# sha2017_rev1_0_0_0.net
KiCad netlist of a schematic drawn in Altium Designer
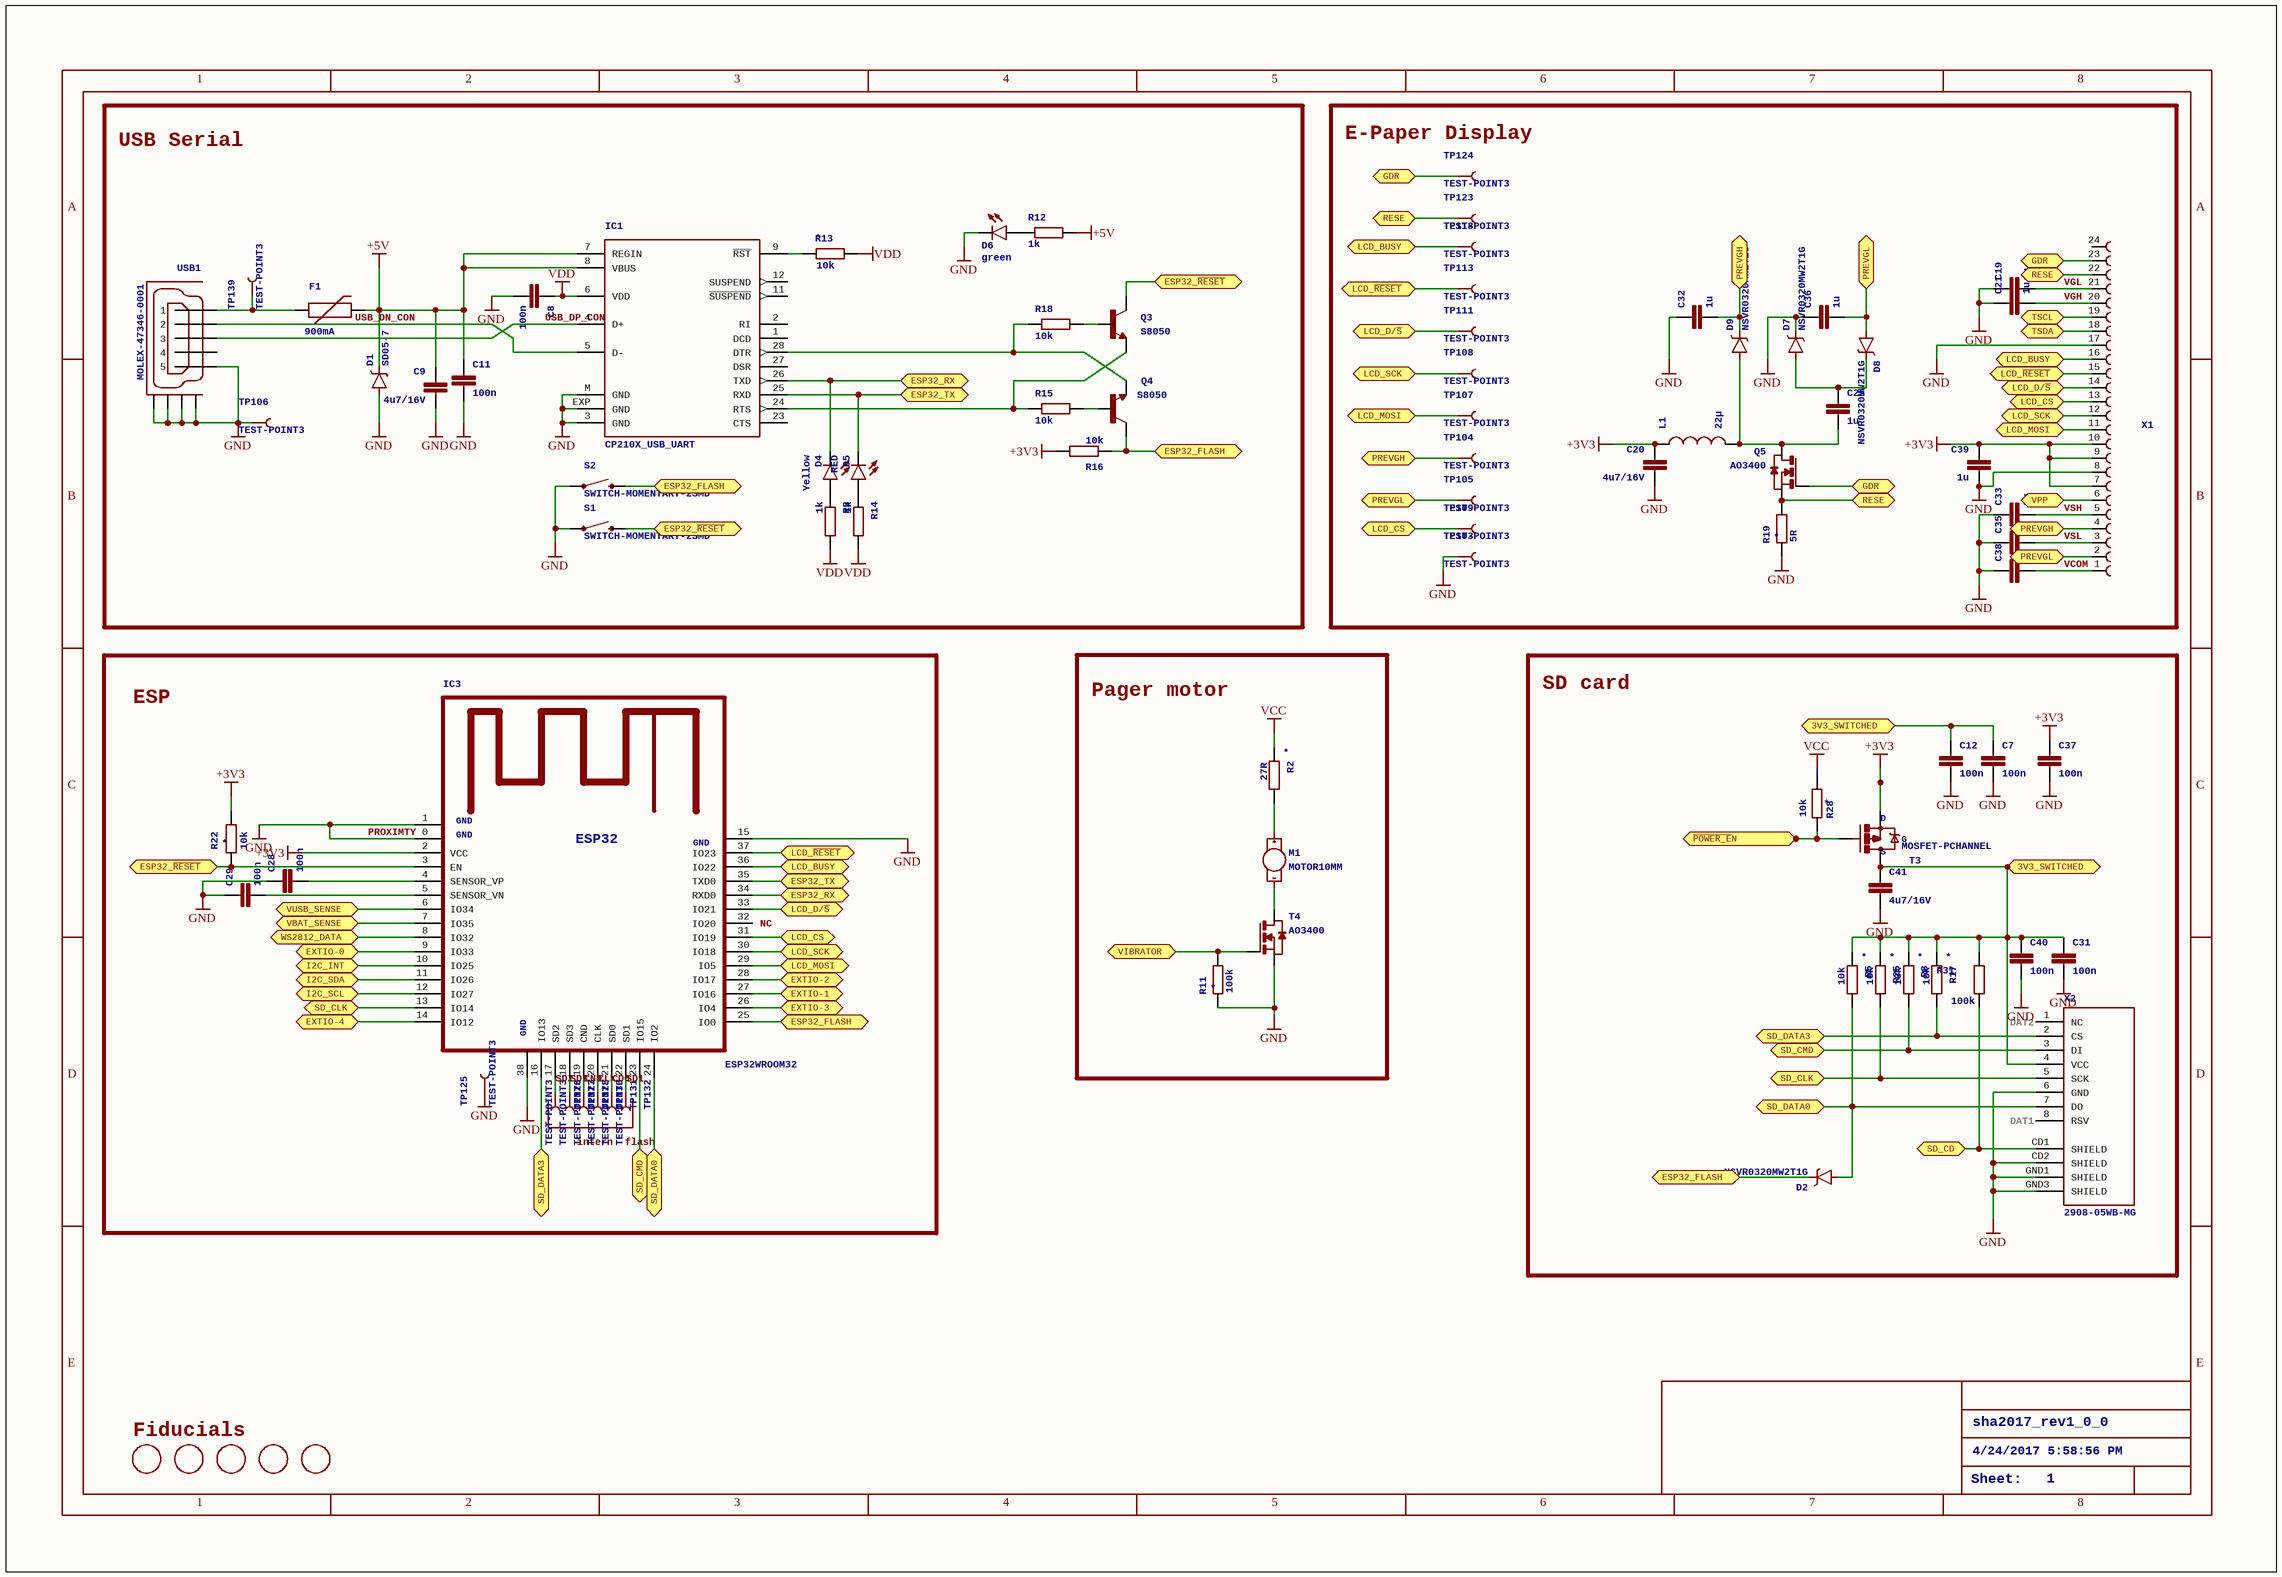
[diagram p0: sha2017_rev1_0_0_0.SchDoc]

(export (version "E")
  (design (tool "Eeschema 10.0.6"))
  (components
    (comp (ref "C7") (value "100n") (footprint "C0603-DASHES") (libsource (lib "") (part "C0603-DASHES_1")))
    (comp (ref "C8") (value "100n") (footprint "C0603-DASHES") (libsource (lib "") (part "C0603-DASHES_2")))
    (comp (ref "C9")
      (value "4u7/16V")
      (footprint "C0805")
      (description "CAPACITOR, European symbol")
      (libsource (lib "rcl") (part "C-EUC0805"))
    )
    (comp (ref "C11") (value "100n") (footprint "C0603-DASHES") (libsource (lib "") (part "C0603-DASHES_1")))
    (comp (ref "C12") (value "100n") (footprint "C0603-DASHES") (libsource (lib "") (part "C0603-DASHES_1")))
    (comp (ref "C19")
      (value "1u")
      (footprint "C0603-DASHES")
      (libsource (lib "sha2017_rev0_1_0_dev") (part "C0603-DASHES"))
    )
    (comp (ref "C20")
      (value "4u7/16V")
      (footprint "C0805")
      (description "CAPACITOR, European symbol")
      (libsource (lib "rcl") (part "C-EUC0805"))
    )
    (comp (ref "C21")
      (value "1u")
      (footprint "C0603-DASHES")
      (libsource (lib "sha2017_rev0_1_0_dev") (part "C0603-DASHES"))
    )
    (comp (ref "C25") (value "1u") (footprint "C0603-DASHES") (libsource (lib "") (part "C0603-DASHES_1")))
    (comp (ref "C28")
      (value "100n")
      (footprint "C0603-DASHES")
      (libsource (lib "sha2017_rev0_1_0_dev") (part "C0603-DASHES"))
    )
    (comp (ref "C29")
      (value "100n")
      (footprint "C0603-DASHES")
      (libsource (lib "sha2017_rev0_1_0_dev") (part "C0603-DASHES"))
    )
    (comp (ref "C31") (value "100n") (footprint "C0603-DASHES") (libsource (lib "") (part "C0603-DASHES_1")))
    (comp (ref "C32")
      (value "1u")
      (footprint "C0603-DASHES")
      (libsource (lib "sha2017_rev0_1_0_dev") (part "C0603-DASHES"))
    )
    (comp (ref "C33")
      (value "1u")
      (footprint "C0603-DASHES")
      (libsource (lib "sha2017_rev0_1_0_dev") (part "C0603-DASHES"))
    )
    (comp (ref "C35")
      (value "1u")
      (footprint "C0603-DASHES")
      (libsource (lib "sha2017_rev0_1_0_dev") (part "C0603-DASHES"))
    )
    (comp (ref "C36")
      (value "1u")
      (footprint "C0603-DASHES")
      (libsource (lib "sha2017_rev0_1_0_dev") (part "C0603-DASHES"))
    )
    (comp (ref "C37") (value "100n") (footprint "C0603-DASHES") (libsource (lib "") (part "C0603-DASHES_1")))
    (comp (ref "C38")
      (value "1u")
      (footprint "C0603-DASHES")
      (libsource (lib "sha2017_rev0_1_0_dev") (part "C0603-DASHES"))
    )
    (comp (ref "C39") (value "1u") (footprint "C0603-DASHES") (libsource (lib "") (part "C0603-DASHES_2")))
    (comp (ref "C40") (value "100n") (footprint "C0603-DASHES") (libsource (lib "") (part "C0603-DASHES_1")))
    (comp (ref "C41")
      (value "4u7/16V")
      (footprint "C0805")
      (description "CAPACITOR, European symbol")
      (libsource (lib "") (part "C-EUC0805_1"))
    )
    (comp (ref "D1")
      (value "SD05-7")
      (footprint "SOD-323")
      (libsource (lib "SparkFun-DiscreteSemi") (part "DIODE-SCHOTTKY-PMEG4005EJ"))
    )
    (comp (ref "D2")
      (value "NSVR0320MW2T1G")
      (footprint "SOD-323")
      (description "23V, 1A Schottky diode, SOD-323 package")
      (libsource (lib "SparkFun-DiscreteSemi") (part "BAT20JFILM"))
    )
    (comp (ref "D4")
      (value "Yellow")
      (footprint "LED-0603")
      (libsource (lib "SparkFun-LED") (part "LED0603"))
    )
    (comp (ref "D5") (value "RED") (footprint "LED-0603") (libsource (lib "SparkFun-LED") (part "LED0603")))
    (comp (ref "D6") (value "green") (footprint "LED-0603") (libsource (lib "SparkFun-LED") (part "LED0603")))
    (comp (ref "D7")
      (value "NSVR0320MW2T1G")
      (footprint "SOD-323")
      (description "23V, 1A Schottky diode, SOD-323 package")
      (libsource (lib "SparkFun-DiscreteSemi") (part "BAT20JFILM"))
    )
    (comp (ref "D8")
      (value "NSVR0320MW2T1G")
      (footprint "SOD-323")
      (description "23V, 1A Schottky diode, SOD-323 package")
      (libsource (lib "SparkFun-DiscreteSemi") (part "BAT20JFILM"))
    )
    (comp (ref "D9")
      (value "NSVR0320MW2T1G")
      (footprint "SOD-323")
      (description "23V, 1A Schottky diode, SOD-323 package")
      (libsource (lib "SparkFun-DiscreteSemi") (part "BAT20JFILM"))
    )
    (comp (ref "F1")
      (value "900mA")
      (footprint "PTC-1206")
      (description "Resettable Fuse PTCResettable Fuse. Spark Fun Electronics SKU : COM-08357")
      (libsource (lib "SparkFun-PowerIC") (part "PTCSMD"))
    )
    (comp (ref "FD1")
      (value "FIDUCIAL")
      (footprint "FIDUCIAL_1MM")
      (description "For use by pick and place machines to calibrate the vision/machine, 1mm    By microbuilder.eu")
      (libsource (lib "adafruit") (part "FIDUCIAL"))
    )
    (comp (ref "FD2")
      (value "FIDUCIAL")
      (footprint "FIDUCIAL_1MM")
      (description "For use by pick and place machines to calibrate the vision/machine, 1mm    By microbuilder.eu")
      (libsource (lib "adafruit") (part "FIDUCIAL"))
    )
    (comp (ref "FD3")
      (value "FIDUCIAL")
      (footprint "FIDUCIAL_1MM")
      (description "For use by pick and place machines to calibrate the vision/machine, 1mm    By microbuilder.eu")
      (libsource (lib "adafruit") (part "FIDUCIAL"))
    )
    (comp (ref "FD4")
      (value "FIDUCIAL")
      (footprint "FIDUCIAL_1MM")
      (description "For use by pick and place machines to calibrate the vision/machine, 1mm    By microbuilder.eu")
      (libsource (lib "adafruit") (part "FIDUCIAL"))
    )
    (comp (ref "FD5")
      (value "FIDUCIAL")
      (footprint "FIDUCIAL_1MM")
      (description "For use by pick and place machines to calibrate the vision/machine, 1mm    By microbuilder.eu")
      (libsource (lib "adafruit") (part "FIDUCIAL"))
    )
    (comp (ref "IC1")
      (value "CP210X_USB_UART")
      (footprint "MLP28")
      (libsource (lib "SparkFun-DigitalIC") (part "CP210X_USB_UART"))
    )
    (comp (ref "IC3")
      (value "ESP32WROOM32")
      (footprint "ESP32MOD")
      (fields
        (field (name "ESP32") "ESP32")
        (field (name "GND") "GND")
        (field (name "GND_1") "GND")
        (field (name "GND_2") "GND")
        (field (name "GND_3") "GND")
      )
      (libsource (lib "ESP3x") (part "ESP32WROOM32"))
    )
    (comp (ref "L1")
      (value "22µ")
      (footprint "1210")
      (libsource (lib "SparkFun-Passives") (part "INDUCTOR1210"))
    )
    (comp (ref "M1")
      (value "MOTOR10MM")
      (footprint "VIBE-MOTOR-10MM")
      (libsource (lib "badge") (part "MOTOR10MM"))
    )
    (comp (ref "Q3")
      (value "S8050")
      (footprint "SOT23-3")
      (libsource (lib "SparkFun-DiscreteSemi") (part "TRANSISTOR_NPNMMBT2222A"))
    )
    (comp (ref "Q4")
      (value "S8050")
      (footprint "SOT23-3")
      (libsource (lib "") (part "TRANSISTOR_NPNMMBT2222A_1"))
    )
    (comp (ref "Q5")
      (value "AO3400")
      (footprint "SOT-23")
      (description "MOS FET")
      (libsource (lib "") (part "NMOSSOT23_1"))
    )
    (comp (ref "R2")
      (value "27R")
      (footprint "R0603-DASHES")
      (fields (field (name "NAME") "*"))
      (libsource (lib "00ralf") (part "R0603-DASHES"))
    )
    (comp (ref "R3")
      (value "1k")
      (footprint "R0603-DASHES")
      (libsource (lib "sha2017_rev0_1_0_dev") (part "R0603-DASHES"))
    )
    (comp (ref "R5")
      (value "10k")
      (footprint "R0603-DASHES")
      (fields (field (name "NAME") "*"))
      (libsource (lib "00ralf") (part "R0603-DASHES"))
    )
    (comp (ref "R8")
      (value "10k")
      (footprint "R0603-DASHES")
      (fields (field (name "NAME") "*"))
      (libsource (lib "00ralf") (part "R0603-DASHES"))
    )
    (comp (ref "R11")
      (value "100k")
      (footprint "R0603-DASHES")
      (fields (field (name "NAME") "*"))
      (libsource (lib "00ralf") (part "R0603-DASHES"))
    )
    (comp (ref "R12")
      (value "1k")
      (footprint "R0603-DASHES")
      (libsource (lib "sha2017_rev0_1_0_dev") (part "R0603-DASHES"))
    )
    (comp (ref "R13")
      (value "10k")
      (footprint "R0603-DASHES")
      (fields (field (name "NAME") "*"))
      (libsource (lib "sha2017_rev0_1_0_dev") (part "R0603-DASHES"))
    )
    (comp (ref "R14")
      (value "1k")
      (footprint "R0603-DASHES")
      (libsource (lib "sha2017_rev0_1_0_dev") (part "R0603-DASHES"))
    )
    (comp (ref "R15")
      (value "10k")
      (footprint "R0603-DASHES")
      (libsource (lib "sha2017_rev0_1_0_dev") (part "R0603-DASHES"))
    )
    (comp (ref "R16")
      (value "10k")
      (footprint "R0603-DASHES")
      (libsource (lib "sha2017_rev0_1_0_dev") (part "R0603-DASHES"))
    )
    (comp (ref "R17")
      (value "10k")
      (footprint "R0603-DASHES")
      (fields (field (name "NAME") "*"))
      (libsource (lib "sha2017_rev0_1_0_dev") (part "R0603-DASHES"))
    )
    (comp (ref "R18")
      (value "10k")
      (footprint "R0603-DASHES")
      (libsource (lib "sha2017_rev0_1_0_dev") (part "R0603-DASHES"))
    )
    (comp (ref "R19")
      (value "5R")
      (footprint "R0603-DASHES")
      (fields (field (name "NAME") "*"))
      (libsource (lib "sha2017_rev0_1_0_dev") (part "R0603-DASHES"))
    )
    (comp (ref "R22")
      (value "10k")
      (footprint "R0603-DASHES")
      (fields (field (name "NAME") "*"))
      (libsource (lib "sha2017_rev0_1_0_dev") (part "R0603-DASHES"))
    )
    (comp (ref "R25")
      (value "10k")
      (footprint "R0603-DASHES")
      (fields (field (name "NAME") "*"))
      (libsource (lib "sha2017_rev0_1_0_dev") (part "R0603-DASHES"))
    )
    (comp (ref "R28")
      (value "10k")
      (footprint "R0603-DASHES")
      (fields (field (name "NAME") "*"))
      (libsource (lib "00ralf") (part "R0603-DASHES"))
    )
    (comp (ref "R31")
      (value "100k")
      (footprint "R0603-DASHES")
      (fields (field (name "NAME") "*"))
      (libsource (lib "sha2017_rev0_1_0_dev") (part "R0603-DASHES"))
    )
    (comp (ref "S1")
      (value "SWITCH-MOMENTARY-2SMD")
      (footprint "TACTILE-SWITCH-SMD")
      (description "Various NO switches- pushbuttons, reed, etc")
      (libsource (lib "SparkFun-Electromechanical") (part "SWITCH-MOMENTARY-2SMD"))
    )
    (comp (ref "S2")
      (value "SWITCH-MOMENTARY-2SMD")
      (footprint "TACTILE-SWITCH-SMD")
      (description "Various NO switches- pushbuttons, reed, etc")
      (libsource (lib "SparkFun-Electromechanical") (part "SWITCH-MOMENTARY-2SMD"))
    )
    (comp (ref "T3")
      (value "MOSFET-PCHANNEL")
      (footprint "SOT23-3")
      (fields (field (name "D") "D") (field (name "S") "S") (field (name "G") "G"))
      (libsource (lib "SparkFun-DiscreteSemi") (part "MOSFET-PCHANNEL"))
    )
    (comp (ref "T4")
      (value "AO3400")
      (footprint "SOT-23")
      (description "MOS FET")
      (libsource (lib "zetex") (part "NMOSSOT23"))
    )
    (comp (ref "TP103")
      (value "TEST-POINT3")
      (footprint "PAD.03X.03")
      (description "Bare copper test points for troubleshooting or ICT")
      (libsource (lib "SparkFun-Passives") (part "TEST-POINT3"))
    )
    (comp (ref "TP104")
      (value "TEST-POINT3")
      (footprint "PAD.03X.03")
      (description "Bare copper test points for troubleshooting or ICT")
      (libsource (lib "SparkFun-Passives") (part "TEST-POINT3"))
    )
    (comp (ref "TP105")
      (value "TEST-POINT3")
      (footprint "PAD.03X.03")
      (description "Bare copper test points for troubleshooting or ICT")
      (libsource (lib "SparkFun-Passives") (part "TEST-POINT3"))
    )
    (comp (ref "TP106")
      (value "TEST-POINT3")
      (footprint "PAD.03X.03")
      (description "Bare copper test points for troubleshooting or ICT")
      (libsource (lib "SparkFun-Passives") (part "TEST-POINT3"))
    )
    (comp (ref "TP107")
      (value "TEST-POINT3")
      (footprint "PAD.03X.03")
      (description "Bare copper test points for troubleshooting or ICT")
      (libsource (lib "SparkFun-Passives") (part "TEST-POINT3"))
    )
    (comp (ref "TP108")
      (value "TEST-POINT3")
      (footprint "PAD.03X.03")
      (description "Bare copper test points for troubleshooting or ICT")
      (libsource (lib "SparkFun-Passives") (part "TEST-POINT3"))
    )
    (comp (ref "TP109")
      (value "TEST-POINT3")
      (footprint "PAD.03X.03")
      (description "Bare copper test points for troubleshooting or ICT")
      (libsource (lib "SparkFun-Passives") (part "TEST-POINT3"))
    )
    (comp (ref "TP111")
      (value "TEST-POINT3")
      (footprint "PAD.03X.03")
      (description "Bare copper test points for troubleshooting or ICT")
      (libsource (lib "SparkFun-Passives") (part "TEST-POINT3"))
    )
    (comp (ref "TP113")
      (value "TEST-POINT3")
      (footprint "PAD.03X.03")
      (description "Bare copper test points for troubleshooting or ICT")
      (libsource (lib "SparkFun-Passives") (part "TEST-POINT3"))
    )
    (comp (ref "TP118")
      (value "TEST-POINT3")
      (footprint "PAD.03X.03")
      (description "Bare copper test points for troubleshooting or ICT")
      (libsource (lib "SparkFun-Passives") (part "TEST-POINT3"))
    )
    (comp (ref "TP123")
      (value "TEST-POINT3")
      (footprint "PAD.03X.03")
      (description "Bare copper test points for troubleshooting or ICT")
      (libsource (lib "SparkFun-Passives") (part "TEST-POINT3"))
    )
    (comp (ref "TP124")
      (value "TEST-POINT3")
      (footprint "PAD.03X.03")
      (description "Bare copper test points for troubleshooting or ICT")
      (libsource (lib "SparkFun-Passives") (part "TEST-POINT3"))
    )
    (comp (ref "TP125")
      (value "TEST-POINT3")
      (footprint "PAD.03X.03")
      (description "Bare copper test points for troubleshooting or ICT")
      (libsource (lib "SparkFun-Passives") (part "TEST-POINT3"))
    )
    (comp (ref "TP126")
      (value "TEST-POINT3")
      (footprint "PAD.03X.03")
      (description "Bare copper test points for troubleshooting or ICT")
      (libsource (lib "SparkFun-Passives") (part "TEST-POINT3"))
    )
    (comp (ref "TP127")
      (value "TEST-POINT3")
      (footprint "PAD.03X.03")
      (description "Bare copper test points for troubleshooting or ICT")
      (libsource (lib "SparkFun-Passives") (part "TEST-POINT3"))
    )
    (comp (ref "TP128")
      (value "TEST-POINT3")
      (footprint "PAD.03X.03")
      (description "Bare copper test points for troubleshooting or ICT")
      (libsource (lib "SparkFun-Passives") (part "TEST-POINT3"))
    )
    (comp (ref "TP130")
      (value "TEST-POINT3")
      (footprint "PAD.03X.03")
      (description "Bare copper test points for troubleshooting or ICT")
      (libsource (lib "SparkFun-Passives") (part "TEST-POINT3"))
    )
    (comp (ref "TP131")
      (value "TEST-POINT3")
      (footprint "PAD.03X.03")
      (description "Bare copper test points for troubleshooting or ICT")
      (libsource (lib "SparkFun-Passives") (part "TEST-POINT3"))
    )
    (comp (ref "TP132")
      (value "TEST-POINT3")
      (footprint "PAD.03X.03")
      (description "Bare copper test points for troubleshooting or ICT")
      (libsource (lib "SparkFun-Passives") (part "TEST-POINT3"))
    )
    (comp (ref "TP139")
      (value "TEST-POINT3")
      (footprint "PAD.03X.03")
      (description "Bare copper test points for troubleshooting or ICT")
      (libsource (lib "SparkFun-Passives") (part "TEST-POINT3"))
    )
    (comp (ref "USB1")
      (value "MOLEX-47346-0001")
      (footprint "MOLEX-47364-0001")
      (description "MICRO USB B, BOTTOM MOUNT")
      (libsource (lib "usb_con-update") (part "MOLEX-47346-0001"))
    )
    (comp (ref "X1")
      (value "68712414022")
      (footprint "68712414022")
      (libsource (lib "EAGLE-FPC_CONNECTOR_AND_FFC_CAB-rev1") (part "68712414022"))
    )
    (comp (ref "X2")
      (value "2908-05WB-MG")
      (footprint "MICRO-SD-SOCKET-PP")
      (libsource (lib "con-3m") (part "2908-05WB-MG"))
    )
  )
  (nets
    (net (code "1") (name "+3V3") (class "Default")
      (node (ref "C20") (pin "1") (pinfunction "1_1") (pintype "passive"))
      (node (ref "C37") (pin "1") (pinfunction "1_1") (pintype "passive"))
      (node (ref "C39") (pin "1") (pinfunction "1_1") (pintype "passive"))
      (node (ref "IC3") (pin "2") (pinfunction "VCC_2") (pintype "power_in"))
      (node (ref "L1") (pin "1") (pinfunction "1_1") (pintype "passive"))
      (node (ref "R16") (pin "2") (pinfunction "2_2") (pintype "passive"))
      (node (ref "R22") (pin "1") (pinfunction "1_1") (pintype "passive"))
      (node (ref "T3") (pin "2") (pinfunction "S_2") (pintype "passive"))
      (node (ref "X1") (pin "10") (pinfunction "10_10") (pintype "passive"))
      (node (ref "X1") (pin "7") (pinfunction "7_7") (pintype "passive"))
      (node (ref "X1") (pin "9") (pinfunction "9_9") (pintype "passive"))
    )
    (net (code "2") (name "+5V") (class "Default")
      (node (ref "C11") (pin "1") (pinfunction "1_1") (pintype "passive"))
      (node (ref "C9") (pin "1") (pinfunction "1_1") (pintype "passive"))
      (node (ref "D1") (pin "C") (pinfunction "C_C") (pintype "passive"))
      (node (ref "F1") (pin "2") (pinfunction "2_2") (pintype "passive"))
      (node (ref "IC1") (pin "7") (pinfunction "REGIN_7") (pintype "passive"))
      (node (ref "IC1") (pin "8") (pinfunction "VBUS_8") (pintype "passive"))
      (node (ref "R12") (pin "2") (pinfunction "2_2") (pintype "passive"))
    )
    (net (code "3") (name "/3V3_SWITCHED") (class "Default")
      (node (ref "C12") (pin "1") (pinfunction "1_1") (pintype "passive"))
      (node (ref "C31") (pin "1") (pinfunction "1_1") (pintype "passive"))
      (node (ref "C40") (pin "1") (pinfunction "1_1") (pintype "passive"))
      (node (ref "C41") (pin "1") (pinfunction "1_1") (pintype "passive"))
      (node (ref "C7") (pin "1") (pinfunction "1_1") (pintype "passive"))
      (node (ref "R17") (pin "2") (pinfunction "2_2") (pintype "passive"))
      (node (ref "R25") (pin "2") (pinfunction "2_2") (pintype "passive"))
      (node (ref "R31") (pin "1") (pinfunction "1_1") (pintype "passive"))
      (node (ref "R5") (pin "2") (pinfunction "2_2") (pintype "passive"))
      (node (ref "R8") (pin "2") (pinfunction "2_2") (pintype "passive"))
      (node (ref "T3") (pin "3") (pinfunction "D_3") (pintype "passive"))
      (node (ref "X2") (pin "4") (pinfunction "VCC_4") (pintype "passive"))
    )
    (net (code "4") (name "/CD0") (class "Default")
      (node (ref "IC3") (pin "21") (pinfunction "SD0_21") (pintype "passive"))
      (node (ref "TP131") (pin "P$1") (pinfunction "1_P$1") (pintype "passive"))
    )
    (net (code "5") (name "/CLK") (class "Default")
      (node (ref "IC3") (pin "20") (pinfunction "CLK_20") (pintype "passive"))
      (node (ref "TP130") (pin "P$1") (pinfunction "1_P$1") (pintype "passive"))
    )
    (net (code "6") (name "/CND") (class "Default")
      (node (ref "IC3") (pin "19") (pinfunction "CND_19") (pintype "passive"))
      (node (ref "TP128") (pin "P$1") (pinfunction "1_P$1") (pintype "passive"))
    )
    (net (code "7") (name "/ESP32_FLASH") (class "Default")
      (node (ref "D2") (pin "C") (pinfunction "C_C") (pintype "passive"))
      (node (ref "IC3") (pin "25") (pinfunction "IO0_25") (pintype "passive"))
      (node (ref "Q4") (pin "3") (pinfunction "C_3") (pintype "passive"))
      (node (ref "R16") (pin "1") (pinfunction "1_1") (pintype "passive"))
      (node (ref "S2") (pin "3") (pinfunction "2_3") (pintype "passive"))
    )
    (net (code "8") (name "/ESP32_RX") (class "Default")
      (node (ref "D4") (pin "C") (pinfunction "C_C") (pintype "passive"))
      (node (ref "IC1") (pin "26") (pinfunction "TXD_26") (pintype "output"))
      (node (ref "IC3") (pin "34") (pinfunction "RXD0_34") (pintype "passive"))
    )
    (net (code "9") (name "/ESP32_TX") (class "Default")
      (node (ref "D5") (pin "C") (pinfunction "C_C") (pintype "passive"))
      (node (ref "IC1") (pin "25") (pinfunction "RXD_25") (pintype "passive"))
      (node (ref "IC3") (pin "35") (pinfunction "TXD0_35") (pintype "passive"))
    )
    (net (code "10") (name "/ESP32_~{RESET}") (class "Default")
      (node (ref "IC3") (pin "3") (pinfunction "EN_3") (pintype "passive"))
      (node (ref "Q3") (pin "3") (pinfunction "C_3") (pintype "passive"))
      (node (ref "R22") (pin "2") (pinfunction "2_2") (pintype "passive"))
      (node (ref "S1") (pin "3") (pinfunction "2_3") (pintype "passive"))
    )
    (net (code "11") (name "/EXTIO-0") (class "Default")
      (node (ref "IC3") (pin "9") (pinfunction "IO33_9") (pintype "passive"))
    )
    (net (code "12") (name "/EXTIO-1") (class "Default")
      (node (ref "IC3") (pin "27") (pinfunction "IO16_27") (pintype "passive"))
    )
    (net (code "13") (name "/EXTIO-2") (class "Default")
      (node (ref "IC3") (pin "28") (pinfunction "IO17_28") (pintype "passive"))
    )
    (net (code "14") (name "/EXTIO-3") (class "Default")
      (node (ref "IC3") (pin "26") (pinfunction "IO4_26") (pintype "passive"))
    )
    (net (code "15") (name "/EXTIO-4") (class "Default")
      (node (ref "IC3") (pin "14") (pinfunction "IO12_14") (pintype "passive"))
    )
    (net (code "16") (name "/GDR") (class "Default")
      (node (ref "Q5") (pin "3") (pinfunction "G_3") (pintype "passive"))
      (node (ref "TP124") (pin "P$1") (pinfunction "1_P$1") (pintype "passive"))
      (node (ref "X1") (pin "23") (pinfunction "23_23") (pintype "passive"))
    )
    (net (code "17") (name "/I2C_INT") (class "Default")
      (node (ref "IC3") (pin "10") (pinfunction "IO25_10") (pintype "passive"))
    )
    (net (code "18") (name "/I2C_SCL") (class "Default")
      (node (ref "IC3") (pin "12") (pinfunction "IO27_12") (pintype "passive"))
    )
    (net (code "19") (name "/I2C_SDA") (class "Default")
      (node (ref "IC3") (pin "11") (pinfunction "IO26_11") (pintype "passive"))
    )
    (net (code "20") (name "/LCD_BUSY") (class "Default")
      (node (ref "IC3") (pin "36") (pinfunction "IO22_36") (pintype "passive"))
      (node (ref "TP118") (pin "P$1") (pinfunction "1_P$1") (pintype "passive"))
      (node (ref "X1") (pin "16") (pinfunction "16_16") (pintype "passive"))
    )
    (net (code "21") (name "/LCD_CS") (class "Default")
      (node (ref "IC3") (pin "31") (pinfunction "IO19_31") (pintype "passive"))
      (node (ref "TP109") (pin "P$1") (pinfunction "1_P$1") (pintype "passive"))
      (node (ref "X1") (pin "13") (pinfunction "13_13") (pintype "passive"))
    )
    (net (code "22") (name "/LCD_D{slash}~{S}") (class "Default")
      (node (ref "IC3") (pin "33") (pinfunction "IO21_33") (pintype "passive"))
      (node (ref "TP111") (pin "P$1") (pinfunction "1_P$1") (pintype "passive"))
      (node (ref "X1") (pin "14") (pinfunction "14_14") (pintype "passive"))
    )
    (net (code "23") (name "/LCD_MOSI") (class "Default")
      (node (ref "IC3") (pin "29") (pinfunction "IO5_29") (pintype "passive"))
      (node (ref "TP107") (pin "P$1") (pinfunction "1_P$1") (pintype "passive"))
      (node (ref "X1") (pin "11") (pinfunction "11_11") (pintype "passive"))
    )
    (net (code "24") (name "/LCD_SCK") (class "Default")
      (node (ref "IC3") (pin "30") (pinfunction "IO18_30") (pintype "passive"))
      (node (ref "TP108") (pin "P$1") (pinfunction "1_P$1") (pintype "passive"))
      (node (ref "X1") (pin "12") (pinfunction "12_12") (pintype "passive"))
    )
    (net (code "25") (name "/LCD_~{RESET}") (class "Default")
      (node (ref "IC3") (pin "37") (pinfunction "IO23_37") (pintype "passive"))
      (node (ref "TP113") (pin "P$1") (pinfunction "1_P$1") (pintype "passive"))
      (node (ref "X1") (pin "15") (pinfunction "15_15") (pintype "passive"))
    )
    (net (code "26") (name "/PREVGH") (class "Default")
      (node (ref "C32") (pin "2") (pinfunction "2_2") (pintype "passive"))
      (node (ref "D9") (pin "C") (pinfunction "C_C") (pintype "passive"))
      (node (ref "TP104") (pin "P$1") (pinfunction "1_P$1") (pintype "passive"))
      (node (ref "X1") (pin "4") (pinfunction "4_4") (pintype "passive"))
    )
    (net (code "27") (name "/PREVGL") (class "Default")
      (node (ref "C36") (pin "2") (pinfunction "2_2") (pintype "passive"))
      (node (ref "D8") (pin "A") (pinfunction "A_A") (pintype "passive"))
      (node (ref "TP105") (pin "P$1") (pinfunction "1_P$1") (pintype "passive"))
      (node (ref "X1") (pin "2") (pinfunction "2_2") (pintype "passive"))
    )
    (net (code "28") (name "/RESE") (class "Default")
      (node (ref "Q5") (pin "2") (pinfunction "S_2") (pintype "passive"))
      (node (ref "R19") (pin "1") (pinfunction "1_1") (pintype "passive"))
      (node (ref "TP123") (pin "P$1") (pinfunction "1_P$1") (pintype "passive"))
      (node (ref "X1") (pin "22") (pinfunction "22_22") (pintype "passive"))
    )
    (net (code "29") (name "/SD1") (class "Default")
      (node (ref "IC3") (pin "22") (pinfunction "SD1_22") (pintype "passive"))
      (node (ref "TP132") (pin "P$1") (pinfunction "1_P$1") (pintype "passive"))
    )
    (net (code "30") (name "/SD2") (class "Default")
      (node (ref "IC3") (pin "17") (pinfunction "SD2_17") (pintype "passive"))
      (node (ref "TP126") (pin "P$1") (pinfunction "1_P$1") (pintype "passive"))
    )
    (net (code "31") (name "/SD3") (class "Default")
      (node (ref "IC3") (pin "18") (pinfunction "SD3_18") (pintype "passive"))
      (node (ref "TP127") (pin "P$1") (pinfunction "1_P$1") (pintype "passive"))
    )
    (net (code "32") (name "/SD_CD") (class "Default")
      (node (ref "R31") (pin "2") (pinfunction "2_2") (pintype "passive"))
      (node (ref "X2") (pin "CD1") (pinfunction "SHIELD_CD1") (pintype "passive"))
    )
    (net (code "33") (name "/SD_CLK") (class "Default")
      (node (ref "IC3") (pin "13") (pinfunction "IO14_13") (pintype "passive"))
      (node (ref "R25") (pin "1") (pinfunction "1_1") (pintype "passive"))
      (node (ref "X2") (pin "5") (pinfunction "SCK_5") (pintype "passive"))
    )
    (net (code "34") (name "/SD_CMD") (class "Default")
      (node (ref "IC3") (pin "23") (pinfunction "IO15_23") (pintype "passive"))
      (node (ref "R8") (pin "1") (pinfunction "1_1") (pintype "passive"))
      (node (ref "X2") (pin "3") (pinfunction "DI_3") (pintype "passive"))
    )
    (net (code "35") (name "/SD_DATA0") (class "Default")
      (node (ref "D2") (pin "A") (pinfunction "A_A") (pintype "passive"))
      (node (ref "IC3") (pin "24") (pinfunction "IO2_24") (pintype "passive"))
      (node (ref "R5") (pin "1") (pinfunction "1_1") (pintype "passive"))
      (node (ref "X2") (pin "7") (pinfunction "DO_7") (pintype "passive"))
    )
    (net (code "36") (name "/SD_DATA3") (class "Default")
      (node (ref "IC3") (pin "16") (pinfunction "IO13_16") (pintype "passive"))
      (node (ref "R17") (pin "1") (pinfunction "1_1") (pintype "passive"))
      (node (ref "X2") (pin "2") (pinfunction "CS_2") (pintype "passive"))
    )
    (net (code "37") (name "/TSCL") (class "Default")
      (node (ref "X1") (pin "19") (pinfunction "19_19") (pintype "passive"))
    )
    (net (code "38") (name "/TSDA") (class "Default")
      (node (ref "X1") (pin "18") (pinfunction "18_18") (pintype "passive"))
    )
    (net (code "39") (name "/USB_DN_CON") (class "Default")
      (node (ref "IC1") (pin "5") (pinfunction "D-_5") (pintype "passive"))
      (node (ref "USB1") (pin "2") (pinfunction "2_2") (pintype "passive"))
    )
    (net (code "40") (name "/USB_DP_CON") (class "Default")
      (node (ref "IC1") (pin "4") (pinfunction "D+_4") (pintype "passive"))
      (node (ref "USB1") (pin "3") (pinfunction "3_3") (pintype "passive"))
    )
    (net (code "41") (name "/VBAT_SENSE") (class "Default")
      (node (ref "IC3") (pin "7") (pinfunction "IO35_7") (pintype "passive"))
    )
    (net (code "42") (name "/VCOM") (class "Default")
      (node (ref "C38") (pin "2") (pinfunction "2_2") (pintype "passive"))
      (node (ref "X1") (pin "1") (pinfunction "1_1") (pintype "passive"))
    )
    (net (code "43") (name "/VGH") (class "Default")
      (node (ref "C21") (pin "2") (pinfunction "2_2") (pintype "passive"))
      (node (ref "X1") (pin "20") (pinfunction "20_20") (pintype "passive"))
    )
    (net (code "44") (name "/VGL") (class "Default")
      (node (ref "C19") (pin "2") (pinfunction "2_2") (pintype "passive"))
      (node (ref "X1") (pin "21") (pinfunction "21_21") (pintype "passive"))
    )
    (net (code "45") (name "/VIBRATOR") (class "Default")
      (node (ref "R11") (pin "1") (pinfunction "1_1") (pintype "passive"))
      (node (ref "T4") (pin "3") (pinfunction "G_3") (pintype "passive"))
    )
    (net (code "46") (name "/VPP") (class "Default")
      (node (ref "X1") (pin "6") (pinfunction "6_6") (pintype "passive"))
    )
    (net (code "47") (name "/VSH") (class "Default")
      (node (ref "C33") (pin "2") (pinfunction "2_2") (pintype "passive"))
      (node (ref "X1") (pin "5") (pinfunction "5_5") (pintype "passive"))
    )
    (net (code "48") (name "/VSL") (class "Default")
      (node (ref "C35") (pin "2") (pinfunction "2_2") (pintype "passive"))
      (node (ref "X1") (pin "3") (pinfunction "3_3") (pintype "passive"))
    )
    (net (code "49") (name "/VUSB_SENSE") (class "Default")
      (node (ref "IC3") (pin "6") (pinfunction "IO34_6") (pintype "passive"))
    )
    (net (code "50") (name "/WS2812_DATA") (class "Default")
      (node (ref "IC3") (pin "8") (pinfunction "IO32_8") (pintype "passive"))
    )
    (net (code "51") (name "/~{POWER_E}N") (class "Default")
      (node (ref "R28") (pin "1") (pinfunction "1_1") (pintype "passive"))
      (node (ref "T3") (pin "1") (pinfunction "G_1") (pintype "passive"))
    )
    (net (code "52") (name "GND") (class "Default")
      (node (ref "C11") (pin "2") (pinfunction "2_2") (pintype "passive"))
      (node (ref "C12") (pin "2") (pinfunction "2_2") (pintype "passive"))
      (node (ref "C19") (pin "1") (pinfunction "1_1") (pintype "passive"))
      (node (ref "C20") (pin "2") (pinfunction "2_2") (pintype "passive"))
      (node (ref "C21") (pin "1") (pinfunction "1_1") (pintype "passive"))
      (node (ref "C28") (pin "1") (pinfunction "1_1") (pintype "passive"))
      (node (ref "C29") (pin "1") (pinfunction "1_1") (pintype "passive"))
      (node (ref "C31") (pin "2") (pinfunction "2_2") (pintype "passive"))
      (node (ref "C32") (pin "1") (pinfunction "1_1") (pintype "passive"))
      (node (ref "C33") (pin "1") (pinfunction "1_1") (pintype "passive"))
      (node (ref "C35") (pin "1") (pinfunction "1_1") (pintype "passive"))
      (node (ref "C36") (pin "1") (pinfunction "1_1") (pintype "passive"))
      (node (ref "C37") (pin "2") (pinfunction "2_2") (pintype "passive"))
      (node (ref "C38") (pin "1") (pinfunction "1_1") (pintype "passive"))
      (node (ref "C39") (pin "2") (pinfunction "2_2") (pintype "passive"))
      (node (ref "C40") (pin "2") (pinfunction "2_2") (pintype "passive"))
      (node (ref "C41") (pin "2") (pinfunction "2_2") (pintype "passive"))
      (node (ref "C7") (pin "2") (pinfunction "2_2") (pintype "passive"))
      (node (ref "C8") (pin "2") (pinfunction "2_2") (pintype "passive"))
      (node (ref "C9") (pin "2") (pinfunction "2_2") (pintype "passive"))
      (node (ref "D1") (pin "A") (pinfunction "A_A") (pintype "passive"))
      (node (ref "D6") (pin "C") (pinfunction "C_C") (pintype "passive"))
      (node (ref "D7") (pin "C") (pinfunction "C_C") (pintype "passive"))
      (node (ref "IC1") (pin "3") (pinfunction "GND_3") (pintype "power_in"))
      (node (ref "IC1") (pin "EXP") (pinfunction "GND_EXP") (pintype "power_in"))
      (node (ref "IC1") (pin "M") (pinfunction "GND_M") (pintype "power_in"))
      (node (ref "IC3") (pin "0") (pinfunction "GND_0") (pintype "power_in"))
      (node (ref "IC3") (pin "1") (pinfunction "GND_1") (pintype "power_in"))
      (node (ref "IC3") (pin "15") (pinfunction "GND_15") (pintype "power_in"))
      (node (ref "IC3") (pin "38") (pinfunction "GND_38") (pintype "power_in"))
      (node (ref "R11") (pin "2") (pinfunction "2_2") (pintype "passive"))
      (node (ref "R19") (pin "2") (pinfunction "2_2") (pintype "passive"))
      (node (ref "S1") (pin "1") (pinfunction "1_1") (pintype "passive"))
      (node (ref "S2") (pin "1") (pinfunction "1_1") (pintype "passive"))
      (node (ref "T4") (pin "2") (pinfunction "S_2") (pintype "passive"))
      (node (ref "TP103") (pin "P$1") (pinfunction "1_P$1") (pintype "passive"))
      (node (ref "TP106") (pin "P$1") (pinfunction "1_P$1") (pintype "passive"))
      (node (ref "TP125") (pin "P$1") (pinfunction "1_P$1") (pintype "passive"))
      (node (ref "USB1") (pin "5") (pinfunction "5_5") (pintype "passive"))
      (node (ref "USB1") (pin "GND1") (pinfunction "GND1_GND1") (pintype "passive"))
      (node (ref "USB1") (pin "GND2") (pinfunction "GND2_GND2") (pintype "passive"))
      (node (ref "USB1") (pin "GND3") (pinfunction "GND3_GND3") (pintype "passive"))
      (node (ref "USB1") (pin "GND4") (pinfunction "GND4_GND4") (pintype "passive"))
      (node (ref "X1") (pin "17") (pinfunction "17_17") (pintype "passive"))
      (node (ref "X1") (pin "8") (pinfunction "8_8") (pintype "passive"))
      (node (ref "X2") (pin "6") (pinfunction "GND_6") (pintype "passive"))
      (node (ref "X2") (pin "CD2") (pinfunction "SHIELD_CD2") (pintype "passive"))
      (node (ref "X2") (pin "GND1") (pinfunction "SHIELD_GND1") (pintype "passive"))
      (node (ref "X2") (pin "GND3") (pinfunction "SHIELD_GND3") (pintype "passive"))
    )
    (net (code "53") (name "Net-(C25-Pad1)") (class "Default")
      (node (ref "C25") (pin "1") (pinfunction "1_1") (pintype "passive"))
      (node (ref "D7") (pin "A") (pinfunction "A_A") (pintype "passive"))
      (node (ref "D8") (pin "C") (pinfunction "C_C") (pintype "passive"))
    )
    (net (code "54") (name "Net-(D4-PadA)") (class "Default")
      (node (ref "D4") (pin "A") (pinfunction "A_A") (pintype "passive"))
      (node (ref "R3") (pin "1") (pinfunction "1_1") (pintype "passive"))
    )
    (net (code "55") (name "Net-(D5-PadA)") (class "Default")
      (node (ref "D5") (pin "A") (pinfunction "A_A") (pintype "passive"))
      (node (ref "R14") (pin "1") (pinfunction "1_1") (pintype "passive"))
    )
    (net (code "56") (name "Net-(D6-PadA)") (class "Default")
      (node (ref "D6") (pin "A") (pinfunction "A_A") (pintype "passive"))
      (node (ref "R12") (pin "1") (pinfunction "1_1") (pintype "passive"))
    )
    (net (code "57") (name "Net-(IC1-DTR)") (class "Default")
      (node (ref "IC1") (pin "28") (pinfunction "DTR_28") (pintype "output"))
      (node (ref "Q4") (pin "2") (pinfunction "E_2") (pintype "passive"))
      (node (ref "R18") (pin "1") (pinfunction "1_1") (pintype "passive"))
    )
    (net (code "58") (name "Net-(IC1-RTS)") (class "Default")
      (node (ref "IC1") (pin "24") (pinfunction "RTS_24") (pintype "output"))
      (node (ref "Q3") (pin "2") (pinfunction "E_2") (pintype "passive"))
      (node (ref "R15") (pin "1") (pinfunction "1_1") (pintype "passive"))
    )
    (net (code "59") (name "Net-(IC1-~{RST})") (class "Default")
      (node (ref "IC1") (pin "9") (pinfunction "~{RST}_9") (pintype "passive"))
      (node (ref "R13") (pin "2") (pinfunction "2_2") (pintype "passive"))
    )
    (net (code "60") (name "Net-(IC3-SENSOR_VN)") (class "Default")
      (node (ref "C29") (pin "2") (pinfunction "2_2") (pintype "passive"))
      (node (ref "IC3") (pin "5") (pinfunction "SENSOR_VN_5") (pintype "passive"))
    )
    (net (code "61") (name "Net-(IC3-SENSOR_VP)") (class "Default")
      (node (ref "C28") (pin "2") (pinfunction "2_2") (pintype "passive"))
      (node (ref "IC3") (pin "4") (pinfunction "SENSOR_VP_4") (pintype "passive"))
    )
    (net (code "62") (name "Net-(M1-Pad+)") (class "Default")
      (node (ref "M1") (pin "+") (pinfunction "+_+") (pintype "passive"))
      (node (ref "R2") (pin "1") (pinfunction "1_1") (pintype "passive"))
    )
    (net (code "63") (name "Net-(Q3-B)") (class "Default")
      (node (ref "Q3") (pin "1") (pinfunction "B_1") (pintype "passive"))
      (node (ref "R18") (pin "2") (pinfunction "2_2") (pintype "passive"))
    )
    (net (code "64") (name "Net-(Q4-B)") (class "Default")
      (node (ref "Q4") (pin "1") (pinfunction "B_1") (pintype "passive"))
      (node (ref "R15") (pin "2") (pinfunction "2_2") (pintype "passive"))
    )
    (net (code "65") (name "Net-(Q5-D)") (class "Default")
      (node (ref "C25") (pin "2") (pinfunction "2_2") (pintype "passive"))
      (node (ref "D9") (pin "A") (pinfunction "A_A") (pintype "passive"))
      (node (ref "L1") (pin "2") (pinfunction "2_2") (pintype "passive"))
      (node (ref "Q5") (pin "1") (pinfunction "D_1") (pintype "passive"))
    )
    (net (code "66") (name "Net-(T4-D)") (class "Default")
      (node (ref "M1") (pin "-") (pinfunction "-_-") (pintype "passive"))
      (node (ref "T4") (pin "1") (pinfunction "D_1") (pintype "passive"))
    )
    (net (code "67") (name "Net-(TP139-1)") (class "Default")
      (node (ref "F1") (pin "1") (pinfunction "1_1") (pintype "passive"))
      (node (ref "TP139") (pin "P$1") (pinfunction "1_P$1") (pintype "passive"))
      (node (ref "USB1") (pin "1") (pinfunction "1_1") (pintype "passive"))
    )
    (net (code "68") (name "VCC") (class "Default")
      (node (ref "R2") (pin "2") (pinfunction "2_2") (pintype "passive"))
      (node (ref "R28") (pin "2") (pinfunction "2_2") (pintype "passive"))
    )
    (net (code "69") (name "VDD") (class "Default")
      (node (ref "C8") (pin "1") (pinfunction "1_1") (pintype "passive"))
      (node (ref "IC1") (pin "6") (pinfunction "VDD_6") (pintype "power_in"))
      (node (ref "R13") (pin "1") (pinfunction "1_1") (pintype "passive"))
      (node (ref "R14") (pin "2") (pinfunction "2_2") (pintype "passive"))
      (node (ref "R3") (pin "2") (pinfunction "2_2") (pintype "passive"))
    )
    (net (code "70") (name "unconnected-(IC1-CTS-Pad23)") (class "Default")
      (node (ref "IC1") (pin "23") (pinfunction "CTS_23") (pintype "passive"))
    )
    (net (code "71") (name "unconnected-(IC1-DCD-Pad1)") (class "Default")
      (node (ref "IC1") (pin "1") (pinfunction "DCD_1") (pintype "passive"))
    )
    (net (code "72") (name "unconnected-(IC1-DSR-Pad27)") (class "Default")
      (node (ref "IC1") (pin "27") (pinfunction "DSR_27") (pintype "passive"))
    )
    (net (code "73") (name "unconnected-(IC1-RI-Pad2)") (class "Default")
      (node (ref "IC1") (pin "2") (pinfunction "RI_2") (pintype "passive"))
    )
    (net (code "74") (name "unconnected-(IC1-SUSPEND-Pad12)") (class "Default")
      (node (ref "IC1") (pin "12") (pinfunction "SUSPEND_12") (pintype "output"))
    )
    (net (code "75") (name "unconnected-(IC1-~{SUSPEND}-Pad11)") (class "Default")
      (node (ref "IC1") (pin "11") (pinfunction "~{SUSPEND}_11") (pintype "output"))
    )
    (net (code "76") (name "unconnected-(IC3-IO20-Pad32)") (class "Default")
      (node (ref "IC3") (pin "32") (pinfunction "IO20_32") (pintype "passive"))
    )
    (net (code "77") (name "unconnected-(USB1-Pad4)") (class "Default")
      (node (ref "USB1") (pin "4") (pinfunction "4_4") (pintype "passive"))
    )
    (net (code "78") (name "unconnected-(X1-Pad24)") (class "Default")
      (node (ref "X1") (pin "24") (pinfunction "24_24") (pintype "passive"))
    )
    (net (code "79") (name "unconnected-(X2-NC-Pad1)") (class "Default")
      (node (ref "X2") (pin "1") (pinfunction "NC_1") (pintype "passive"))
    )
    (net (code "80") (name "unconnected-(X2-RSV-Pad8)") (class "Default")
      (node (ref "X2") (pin "8") (pinfunction "RSV_8") (pintype "passive"))
    )
  )
)
